# electron-power-bq24298.net
KiCad netlist of a schematic drawn in EAGLE
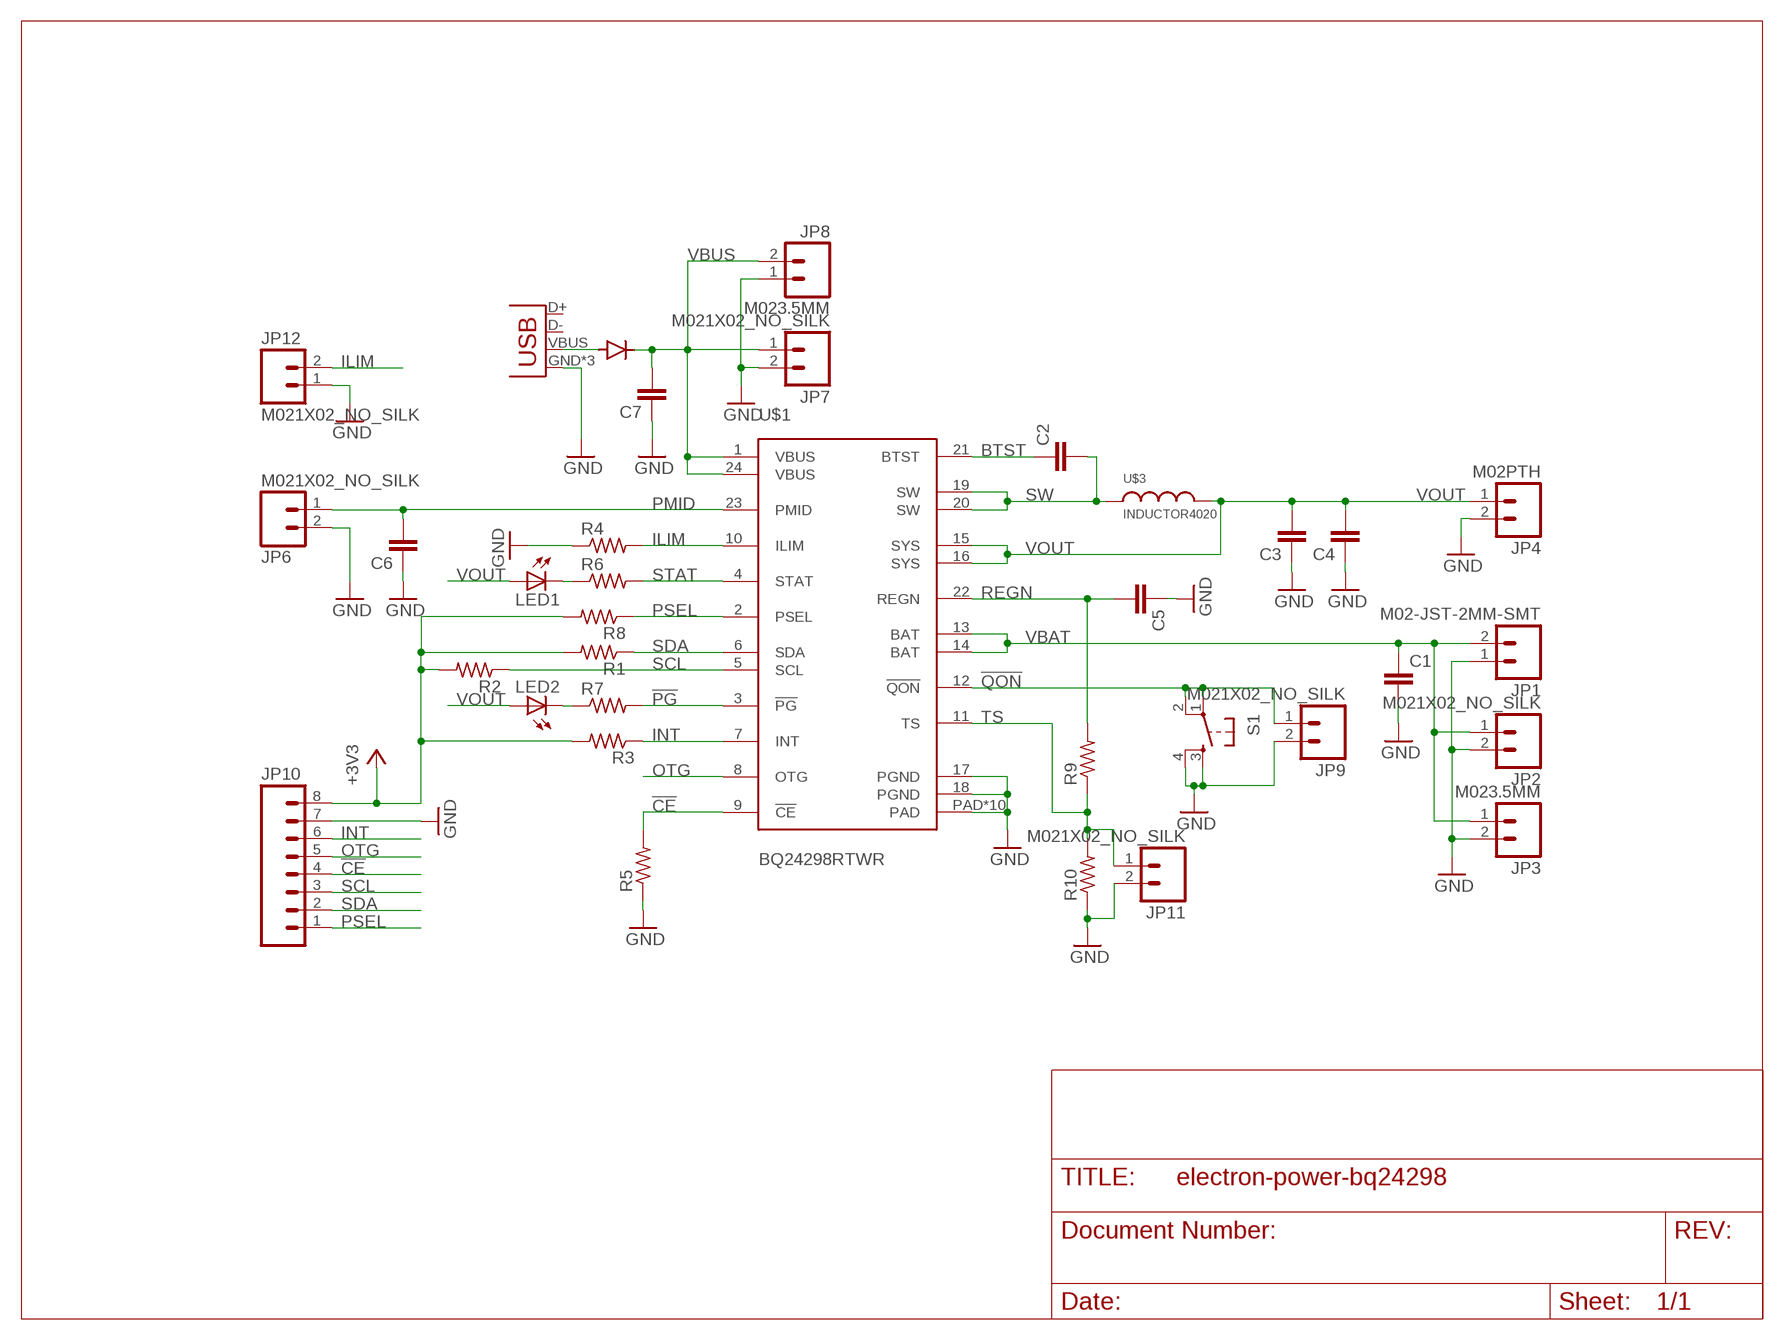
[diagram p0: schematic, sheet 1]

(export (version "E")
  (design (tool "Eeschema 10.0.6"))
  (components
    (comp (ref "C1")
      (value "C-EUC0805")
      (footprint "eagle-import:C0805")
      (libsource (lib "eagle-import") (part "C-EUC0805"))
    )
    (comp (ref "C2")
      (value "C-EUC0402")
      (footprint "eagle-import:C0402")
      (libsource (lib "eagle-import") (part "C-EUC0402"))
    )
    (comp (ref "C3")
      (value "C-EUC0805")
      (footprint "eagle-import:C0805")
      (libsource (lib "eagle-import") (part "C-EUC0805"))
    )
    (comp (ref "C4")
      (value "C-EUC0805")
      (footprint "eagle-import:C0805")
      (libsource (lib "eagle-import") (part "C-EUC0805"))
    )
    (comp (ref "C5")
      (value "C-EUC0402")
      (footprint "eagle-import:C0402")
      (libsource (lib "eagle-import") (part "C-EUC0402"))
    )
    (comp (ref "C6")
      (value "C-EUC0805")
      (footprint "eagle-import:C0805")
      (libsource (lib "eagle-import") (part "C-EUC0805"))
    )
    (comp (ref "C7")
      (value "C-EUC0805")
      (footprint "eagle-import:C0805")
      (libsource (lib "eagle-import") (part "C-EUC0805"))
    )
    (comp (ref "JP1")
      (value "M02-JST-2MM-SMT")
      (footprint "eagle-import:JST-2-SMD")
      (libsource (lib "eagle-import") (part "M02-JST-2MM-SMT"))
    )
    (comp (ref "JP2")
      (value "M021X02_NO_SILK")
      (footprint "eagle-import:1X02_NO_SILK")
      (libsource (lib "eagle-import") (part "M021X02_NO_SILK"))
    )
    (comp (ref "JP3")
      (value "M023.5MM")
      (footprint "eagle-import:SCREWTERMINAL-3.5MM-2")
      (libsource (lib "eagle-import") (part "M023.5MM"))
    )
    (comp (ref "JP4")
      (value "M02PTH")
      (footprint "eagle-import:1X02")
      (libsource (lib "eagle-import") (part "M02PTH"))
    )
    (comp (ref "JP5")
      (value "USBUSB-MICROB-SLOT-HOLE")
      (footprint "eagle-import:USB-MICROB-SLOT-HOLE")
      (libsource (lib "eagle-import") (part "USBUSB-MICROB-SLOT-HOLE"))
    )
    (comp (ref "JP6")
      (value "M021X02_NO_SILK")
      (footprint "eagle-import:1X02_NO_SILK")
      (libsource (lib "eagle-import") (part "M021X02_NO_SILK"))
    )
    (comp (ref "JP7")
      (value "M021X02_NO_SILK")
      (footprint "eagle-import:1X02_NO_SILK")
      (libsource (lib "eagle-import") (part "M021X02_NO_SILK"))
    )
    (comp (ref "JP8")
      (value "M023.5MM")
      (footprint "eagle-import:SCREWTERMINAL-3.5MM-2")
      (libsource (lib "eagle-import") (part "M023.5MM"))
    )
    (comp (ref "JP9")
      (value "M021X02_NO_SILK")
      (footprint "eagle-import:1X02_NO_SILK")
      (libsource (lib "eagle-import") (part "M021X02_NO_SILK"))
    )
    (comp (ref "JP10")
      (value "M08NO_SILK")
      (footprint "eagle-import:1X08_NO_SILK")
      (libsource (lib "eagle-import") (part "M08NO_SILK"))
    )
    (comp (ref "JP11")
      (value "M021X02_NO_SILK")
      (footprint "eagle-import:1X02_NO_SILK")
      (libsource (lib "eagle-import") (part "M021X02_NO_SILK"))
    )
    (comp (ref "JP12")
      (value "M021X02_NO_SILK")
      (footprint "eagle-import:1X02_NO_SILK")
      (libsource (lib "eagle-import") (part "M021X02_NO_SILK"))
    )
    (comp (ref "LED1")
      (value "LEDSML0805")
      (footprint "eagle-import:SML0805")
      (libsource (lib "eagle-import") (part "LEDSML0805"))
    )
    (comp (ref "LED2")
      (value "LEDSML0805")
      (footprint "eagle-import:SML0805")
      (libsource (lib "eagle-import") (part "LEDSML0805"))
    )
    (comp (ref "R1")
      (value "R-US_R0402")
      (footprint "eagle-import:R0402")
      (libsource (lib "eagle-import") (part "R-US_R0402"))
    )
    (comp (ref "R2")
      (value "R-US_R0402")
      (footprint "eagle-import:R0402")
      (libsource (lib "eagle-import") (part "R-US_R0402"))
    )
    (comp (ref "R3")
      (value "R-US_R0402")
      (footprint "eagle-import:R0402")
      (libsource (lib "eagle-import") (part "R-US_R0402"))
    )
    (comp (ref "R4")
      (value "R-US_R0402")
      (footprint "eagle-import:R0402")
      (libsource (lib "eagle-import") (part "R-US_R0402"))
    )
    (comp (ref "R5")
      (value "R-US_R0402")
      (footprint "eagle-import:R0402")
      (libsource (lib "eagle-import") (part "R-US_R0402"))
    )
    (comp (ref "R6")
      (value "R-US_R0402")
      (footprint "eagle-import:R0402")
      (libsource (lib "eagle-import") (part "R-US_R0402"))
    )
    (comp (ref "R7")
      (value "R-US_R0402")
      (footprint "eagle-import:R0402")
      (libsource (lib "eagle-import") (part "R-US_R0402"))
    )
    (comp (ref "R8")
      (value "R-US_R0402")
      (footprint "eagle-import:R0402")
      (libsource (lib "eagle-import") (part "R-US_R0402"))
    )
    (comp (ref "R9")
      (value "R-US_R0402")
      (footprint "eagle-import:R0402")
      (libsource (lib "eagle-import") (part "R-US_R0402"))
    )
    (comp (ref "R10")
      (value "R-US_R0402")
      (footprint "eagle-import:R0402")
      (libsource (lib "eagle-import") (part "R-US_R0402"))
    )
    (comp (ref "S1")
      (value "TAC_SWITCHSMD")
      (footprint "eagle-import:TACTILE_SWITCH_SMD")
      (libsource (lib "eagle-import") (part "TAC_SWITCHSMD"))
    )
    (comp (ref "U$1")
      (value "BQ24298RTWR")
      (footprint "eagle-import:QFN24")
      (libsource (lib "eagle-import") (part "BQ24298RTWR"))
    )
    (comp (ref "U$2")
      (value "DIODE")
      (footprint "eagle-import:DIODE-DO-220AA(SMP)")
      (libsource (lib "eagle-import") (part "DIODE"))
    )
    (comp (ref "U$3")
      (value "INDUCTOR4020")
      (footprint "eagle-import:4020TYPE")
      (libsource (lib "eagle-import") (part "INDUCTOR4020"))
    )
  )
  (nets
    (net (code "1") (name "+3V3") (class "Default")
      (node (ref "JP10") (pin "8") (pinfunction "8_8") (pintype "passive"))
      (node (ref "R1") (pin "2") (pinfunction "2_2") (pintype "passive"))
      (node (ref "R2") (pin "2") (pinfunction "2_2") (pintype "passive"))
      (node (ref "R3") (pin "2") (pinfunction "2_2") (pintype "passive"))
      (node (ref "R8") (pin "2") (pinfunction "2_2") (pintype "passive"))
    )
    (net (code "2") (name "/BTST") (class "Default")
      (node (ref "C2") (pin "1") (pinfunction "1_1") (pintype "passive"))
      (node (ref "U$1") (pin "21") (pinfunction "BTST_21") (pintype "bidirectional"))
    )
    (net (code "3") (name "/ILIM") (class "Default")
      (node (ref "JP12") (pin "2") (pinfunction "2_2") (pintype "passive"))
      (node (ref "R4") (pin "2") (pinfunction "2_2") (pintype "passive"))
      (node (ref "U$1") (pin "10") (pinfunction "ILIM_10") (pintype "output"))
    )
    (net (code "4") (name "/INT") (class "Default")
      (node (ref "JP10") (pin "6") (pinfunction "6_6") (pintype "passive"))
      (node (ref "R3") (pin "1") (pinfunction "1_1") (pintype "passive"))
      (node (ref "U$1") (pin "7") (pinfunction "INT_7") (pintype "bidirectional"))
    )
    (net (code "5") (name "/OTG") (class "Default")
      (node (ref "JP10") (pin "5") (pinfunction "5_5") (pintype "passive"))
      (node (ref "U$1") (pin "8") (pinfunction "OTG_8") (pintype "bidirectional"))
    )
    (net (code "6") (name "/PMID") (class "Default")
      (node (ref "C6") (pin "2") (pinfunction "2_2") (pintype "passive"))
      (node (ref "JP6") (pin "1") (pinfunction "1_1") (pintype "passive"))
      (node (ref "U$1") (pin "23") (pinfunction "PMID_23") (pintype "passive"))
    )
    (net (code "7") (name "/PSEL") (class "Default")
      (node (ref "JP10") (pin "1") (pinfunction "1_1") (pintype "passive"))
      (node (ref "R8") (pin "1") (pinfunction "1_1") (pintype "passive"))
      (node (ref "U$1") (pin "2") (pinfunction "PSEL_2") (pintype "output"))
    )
    (net (code "8") (name "/REGN") (class "Default")
      (node (ref "C5") (pin "2") (pinfunction "2_2") (pintype "passive"))
      (node (ref "R9") (pin "2") (pinfunction "2_2") (pintype "passive"))
      (node (ref "U$1") (pin "22") (pinfunction "REGN_22") (pintype "bidirectional"))
    )
    (net (code "9") (name "/SCL") (class "Default")
      (node (ref "JP10") (pin "3") (pinfunction "3_3") (pintype "passive"))
      (node (ref "R2") (pin "1") (pinfunction "1_1") (pintype "passive"))
      (node (ref "U$1") (pin "5") (pinfunction "SCL_5") (pintype "output"))
    )
    (net (code "10") (name "/SDA") (class "Default")
      (node (ref "JP10") (pin "2") (pinfunction "2_2") (pintype "passive"))
      (node (ref "R1") (pin "1") (pinfunction "1_1") (pintype "passive"))
      (node (ref "U$1") (pin "6") (pinfunction "SDA_6") (pintype "bidirectional"))
    )
    (net (code "11") (name "/STAT") (class "Default")
      (node (ref "R6") (pin "2") (pinfunction "2_2") (pintype "passive"))
      (node (ref "U$1") (pin "4") (pinfunction "STAT_4") (pintype "bidirectional"))
    )
    (net (code "12") (name "/SW") (class "Default")
      (node (ref "C2") (pin "2") (pinfunction "2_2") (pintype "passive"))
      (node (ref "U$1") (pin "19") (pinfunction "SW_19") (pintype "power_in"))
      (node (ref "U$1") (pin "20") (pinfunction "SW_20") (pintype "power_in"))
      (node (ref "U$3") (pin "P$1") (pinfunction "1_P$1") (pintype "bidirectional"))
    )
    (net (code "13") (name "/TS") (class "Default")
      (node (ref "JP11") (pin "1") (pinfunction "1_1") (pintype "passive"))
      (node (ref "R10") (pin "2") (pinfunction "2_2") (pintype "passive"))
      (node (ref "R9") (pin "1") (pinfunction "1_1") (pintype "passive"))
      (node (ref "U$1") (pin "11") (pinfunction "TS_11") (pintype "bidirectional"))
    )
    (net (code "14") (name "/VBAT") (class "Default")
      (node (ref "C1") (pin "1") (pinfunction "1_1") (pintype "passive"))
      (node (ref "JP1") (pin "2") (pinfunction "1_2") (pintype "passive"))
      (node (ref "JP2") (pin "1") (pinfunction "1_1") (pintype "passive"))
      (node (ref "JP3") (pin "1") (pinfunction "1_1") (pintype "passive"))
      (node (ref "U$1") (pin "13") (pinfunction "BAT_13") (pintype "passive"))
      (node (ref "U$1") (pin "14") (pinfunction "BAT_14") (pintype "power_in"))
    )
    (net (code "15") (name "/VBUS") (class "Default")
      (node (ref "C7") (pin "2") (pinfunction "2_2") (pintype "passive"))
      (node (ref "JP7") (pin "1") (pinfunction "1_1") (pintype "passive"))
      (node (ref "JP8") (pin "2") (pinfunction "2_2") (pintype "passive"))
      (node (ref "U$1") (pin "1") (pinfunction "VBUS_1") (pintype "power_in"))
      (node (ref "U$1") (pin "24") (pinfunction "VBUS_24") (pintype "passive"))
      (node (ref "U$2") (pin "CATHODE") (pinfunction "CATHODE_CATHODE") (pintype "bidirectional"))
    )
    (net (code "16") (name "/VOUT") (class "Default")
      (node (ref "C3") (pin "2") (pinfunction "2_2") (pintype "passive"))
      (node (ref "C4") (pin "2") (pinfunction "2_2") (pintype "passive"))
      (node (ref "JP4") (pin "1") (pinfunction "1_1") (pintype "passive"))
      (node (ref "LED1") (pin "A") (pinfunction "A_A") (pintype "passive"))
      (node (ref "LED2") (pin "A") (pinfunction "A_A") (pintype "passive"))
      (node (ref "U$1") (pin "15") (pinfunction "SYS_15") (pintype "power_in"))
      (node (ref "U$1") (pin "16") (pinfunction "SYS_16") (pintype "power_in"))
      (node (ref "U$3") (pin "P$2") (pinfunction "2_P$2") (pintype "bidirectional"))
    )
    (net (code "17") (name "/~{CE}") (class "Default")
      (node (ref "JP10") (pin "4") (pinfunction "4_4") (pintype "passive"))
      (node (ref "R5") (pin "2") (pinfunction "2_2") (pintype "passive"))
      (node (ref "U$1") (pin "9") (pinfunction "~{CE}_9") (pintype "output"))
    )
    (net (code "18") (name "/~{PG}") (class "Default")
      (node (ref "R7") (pin "2") (pinfunction "2_2") (pintype "passive"))
      (node (ref "U$1") (pin "3") (pinfunction "~{PG}_3") (pintype "output"))
    )
    (net (code "19") (name "/~{QON}") (class "Default")
      (node (ref "JP9") (pin "1") (pinfunction "1_1") (pintype "passive"))
      (node (ref "S1") (pin "1") (pinfunction "1_1") (pintype "passive"))
      (node (ref "S1") (pin "2") (pinfunction "2_2") (pintype "passive"))
      (node (ref "U$1") (pin "12") (pinfunction "~{QON}_12") (pintype "bidirectional"))
    )
    (net (code "20") (name "GND") (class "Default")
      (node (ref "C1") (pin "2") (pinfunction "2_2") (pintype "passive"))
      (node (ref "C3") (pin "1") (pinfunction "1_1") (pintype "passive"))
      (node (ref "C4") (pin "1") (pinfunction "1_1") (pintype "passive"))
      (node (ref "C5") (pin "1") (pinfunction "1_1") (pintype "passive"))
      (node (ref "C6") (pin "1") (pinfunction "1_1") (pintype "passive"))
      (node (ref "C7") (pin "1") (pinfunction "1_1") (pintype "passive"))
      (node (ref "JP1") (pin "1") (pinfunction "2_1") (pintype "passive"))
      (node (ref "JP10") (pin "7") (pinfunction "7_7") (pintype "passive"))
      (node (ref "JP11") (pin "2") (pinfunction "2_2") (pintype "passive"))
      (node (ref "JP12") (pin "1") (pinfunction "1_1") (pintype "passive"))
      (node (ref "JP2") (pin "2") (pinfunction "2_2") (pintype "passive"))
      (node (ref "JP3") (pin "2") (pinfunction "2_2") (pintype "passive"))
      (node (ref "JP4") (pin "2") (pinfunction "2_2") (pintype "passive"))
      (node (ref "JP5") (pin "GND") (pinfunction "GND_GND") (pintype "bidirectional"))
      (node (ref "JP5") (pin "MT1") (pinfunction "GND_MT1") (pintype "bidirectional"))
      (node (ref "JP5") (pin "MT2") (pinfunction "GND_MT2") (pintype "bidirectional"))
      (node (ref "JP6") (pin "2") (pinfunction "2_2") (pintype "passive"))
      (node (ref "JP7") (pin "2") (pinfunction "2_2") (pintype "passive"))
      (node (ref "JP8") (pin "1") (pinfunction "1_1") (pintype "passive"))
      (node (ref "JP9") (pin "2") (pinfunction "2_2") (pintype "passive"))
      (node (ref "R10") (pin "1") (pinfunction "1_1") (pintype "passive"))
      (node (ref "R4") (pin "1") (pinfunction "1_1") (pintype "passive"))
      (node (ref "R5") (pin "1") (pinfunction "1_1") (pintype "passive"))
      (node (ref "S1") (pin "3") (pinfunction "3_3") (pintype "passive"))
      (node (ref "S1") (pin "4") (pinfunction "4_4") (pintype "passive"))
      (node (ref "U$1") (pin "17") (pinfunction "PGND_17") (pintype "passive"))
      (node (ref "U$1") (pin "18") (pinfunction "PGND_18") (pintype "passive"))
      (node (ref "U$1") (pin "PAD") (pinfunction "PAD_PAD") (pintype "power_in"))
      (node (ref "U$1") (pin "PAD@1") (pinfunction "PAD_PAD@1") (pintype "power_in"))
      (node (ref "U$1") (pin "PAD@2") (pinfunction "PAD_PAD@2") (pintype "power_in"))
      (node (ref "U$1") (pin "PAD@3") (pinfunction "PAD_PAD@3") (pintype "power_in"))
      (node (ref "U$1") (pin "PAD@4") (pinfunction "PAD_PAD@4") (pintype "power_in"))
      (node (ref "U$1") (pin "PAD@5") (pinfunction "PAD_PAD@5") (pintype "power_in"))
      (node (ref "U$1") (pin "PAD@6") (pinfunction "PAD_PAD@6") (pintype "power_in"))
      (node (ref "U$1") (pin "PAD@7") (pinfunction "PAD_PAD@7") (pintype "power_in"))
      (node (ref "U$1") (pin "PAD@8") (pinfunction "PAD_PAD@8") (pintype "power_in"))
      (node (ref "U$1") (pin "PAD@9") (pinfunction "PAD_PAD@9") (pintype "power_in"))
    )
    (net (code "21") (name "Net-(JP5-PadVBUS)") (class "Default")
      (node (ref "JP5") (pin "VBUS") (pinfunction "VBUS_VBUS") (pintype "bidirectional"))
      (node (ref "U$2") (pin "ANODE") (pinfunction "ANODE_ANODE") (pintype "bidirectional"))
    )
    (net (code "22") (name "Net-(LED1-PadC)") (class "Default")
      (node (ref "LED1") (pin "C") (pinfunction "C_C") (pintype "passive"))
      (node (ref "R6") (pin "1") (pinfunction "1_1") (pintype "passive"))
    )
    (net (code "23") (name "Net-(LED2-PadC)") (class "Default")
      (node (ref "LED2") (pin "C") (pinfunction "C_C") (pintype "passive"))
      (node (ref "R7") (pin "1") (pinfunction "1_1") (pintype "passive"))
    )
    (net (code "24") (name "unconnected-(JP5-PadD+)") (class "Default")
      (node (ref "JP5") (pin "D+") (pinfunction "D+_D+") (pintype "bidirectional"))
    )
    (net (code "25") (name "unconnected-(JP5-PadD-)") (class "Default")
      (node (ref "JP5") (pin "D-") (pinfunction "D-_D-") (pintype "bidirectional"))
    )
  )
)
